# lrdboard_358v1.net
KiCad netlist of a schematic drawn in EAGLE
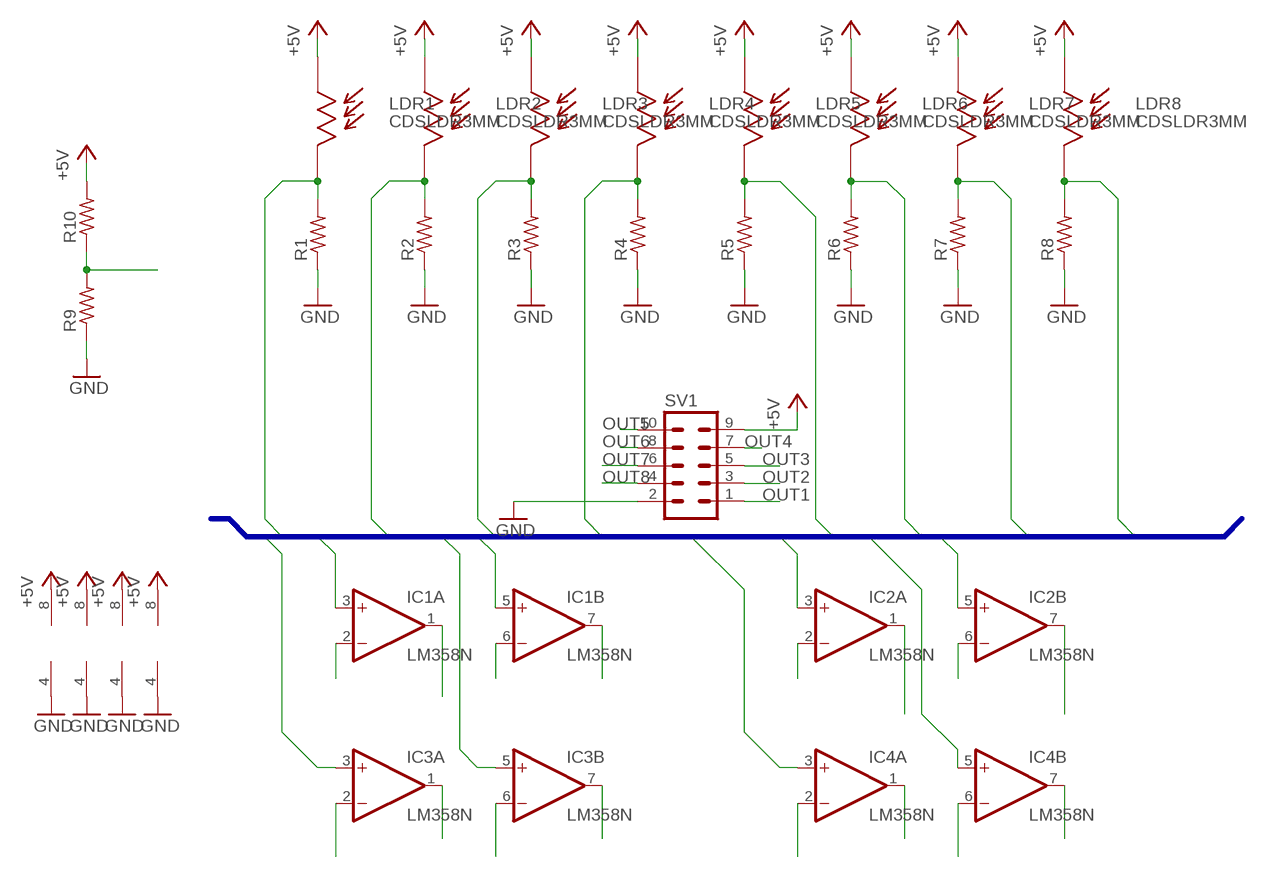
[diagram p0: schematic, sheet 1]

(export (version "E")
  (design (tool "Eeschema 10.0.6"))
  (components
    (comp (ref "IC1")
      (value "LM358N")
      (footprint "eagle-import:DIL08")
      (libsource (lib "eagle-import") (part "LM358N"))
    )
    (comp (ref "IC2")
      (value "LM358N")
      (footprint "eagle-import:DIL08")
      (libsource (lib "eagle-import") (part "LM358N"))
    )
    (comp (ref "IC3")
      (value "LM358N")
      (footprint "eagle-import:DIL08")
      (libsource (lib "eagle-import") (part "LM358N"))
    )
    (comp (ref "IC4")
      (value "LM358N")
      (footprint "eagle-import:DIL08")
      (libsource (lib "eagle-import") (part "LM358N"))
    )
    (comp (ref "LDR1")
      (value "CDSLDR3MM")
      (footprint "eagle-import:LDR3MM")
      (libsource (lib "eagle-import") (part "CDSLDR3MM"))
    )
    (comp (ref "LDR2")
      (value "CDSLDR3MM")
      (footprint "eagle-import:LDR3MM")
      (libsource (lib "eagle-import") (part "CDSLDR3MM"))
    )
    (comp (ref "LDR3")
      (value "CDSLDR3MM")
      (footprint "eagle-import:LDR3MM")
      (libsource (lib "eagle-import") (part "CDSLDR3MM"))
    )
    (comp (ref "LDR4")
      (value "CDSLDR3MM")
      (footprint "eagle-import:LDR3MM")
      (libsource (lib "eagle-import") (part "CDSLDR3MM"))
    )
    (comp (ref "LDR5")
      (value "CDSLDR3MM")
      (footprint "eagle-import:LDR3MM")
      (libsource (lib "eagle-import") (part "CDSLDR3MM"))
    )
    (comp (ref "LDR6")
      (value "CDSLDR3MM")
      (footprint "eagle-import:LDR3MM")
      (libsource (lib "eagle-import") (part "CDSLDR3MM"))
    )
    (comp (ref "LDR7")
      (value "CDSLDR3MM")
      (footprint "eagle-import:LDR3MM")
      (libsource (lib "eagle-import") (part "CDSLDR3MM"))
    )
    (comp (ref "LDR8")
      (value "CDSLDR3MM")
      (footprint "eagle-import:LDR3MM")
      (libsource (lib "eagle-import") (part "CDSLDR3MM"))
    )
    (comp (ref "R1")
      (value "RESISTOR0207/10")
      (footprint "eagle-import:0207_10")
      (libsource (lib "eagle-import") (part "RESISTOR0207/10"))
    )
    (comp (ref "R2")
      (value "RESISTOR0207/10")
      (footprint "eagle-import:0207_10")
      (libsource (lib "eagle-import") (part "RESISTOR0207/10"))
    )
    (comp (ref "R3")
      (value "RESISTOR0207/10")
      (footprint "eagle-import:0207_10")
      (libsource (lib "eagle-import") (part "RESISTOR0207/10"))
    )
    (comp (ref "R4")
      (value "RESISTOR0207/10")
      (footprint "eagle-import:0207_10")
      (libsource (lib "eagle-import") (part "RESISTOR0207/10"))
    )
    (comp (ref "R5")
      (value "RESISTOR0207/10")
      (footprint "eagle-import:0207_10")
      (libsource (lib "eagle-import") (part "RESISTOR0207/10"))
    )
    (comp (ref "R6")
      (value "RESISTOR0207/10")
      (footprint "eagle-import:0207_10")
      (libsource (lib "eagle-import") (part "RESISTOR0207/10"))
    )
    (comp (ref "R7")
      (value "RESISTOR0207/10")
      (footprint "eagle-import:0207_10")
      (libsource (lib "eagle-import") (part "RESISTOR0207/10"))
    )
    (comp (ref "R8")
      (value "RESISTOR0207/10")
      (footprint "eagle-import:0207_10")
      (libsource (lib "eagle-import") (part "RESISTOR0207/10"))
    )
    (comp (ref "R9")
      (value "RESISTOR0207/10")
      (footprint "eagle-import:0207_10")
      (libsource (lib "eagle-import") (part "RESISTOR0207/10"))
    )
    (comp (ref "R10")
      (value "RESISTOR0207/10")
      (footprint "eagle-import:0207_10")
      (libsource (lib "eagle-import") (part "RESISTOR0207/10"))
    )
    (comp (ref "SV1")
      (value "MA05-2")
      (footprint "eagle-import:MA05-2")
      (libsource (lib "eagle-import") (part "MA05-2"))
    )
  )
  (nets
    (net (code "1") (name "+5V") (class "Default")
      (node (ref "IC1") (pin "8") (pinfunction "V+_8") (pintype "power_in"))
      (node (ref "IC2") (pin "8") (pinfunction "V+_8") (pintype "power_in"))
      (node (ref "IC3") (pin "8") (pinfunction "V+_8") (pintype "power_in"))
      (node (ref "IC4") (pin "8") (pinfunction "V+_8") (pintype "power_in"))
      (node (ref "LDR1") (pin "P$1") (pinfunction "P$1_P$1") (pintype "bidirectional"))
      (node (ref "LDR2") (pin "P$1") (pinfunction "P$1_P$1") (pintype "bidirectional"))
      (node (ref "LDR3") (pin "P$1") (pinfunction "P$1_P$1") (pintype "bidirectional"))
      (node (ref "LDR4") (pin "P$1") (pinfunction "P$1_P$1") (pintype "bidirectional"))
      (node (ref "LDR5") (pin "P$1") (pinfunction "P$1_P$1") (pintype "bidirectional"))
      (node (ref "LDR6") (pin "P$1") (pinfunction "P$1_P$1") (pintype "bidirectional"))
      (node (ref "LDR7") (pin "P$1") (pinfunction "P$1_P$1") (pintype "bidirectional"))
      (node (ref "LDR8") (pin "P$1") (pinfunction "P$1_P$1") (pintype "bidirectional"))
      (node (ref "R10") (pin "2") (pinfunction "2_2") (pintype "passive"))
      (node (ref "SV1") (pin "9") (pinfunction "9_9") (pintype "passive"))
    )
    (net (code "2") (name "/1") (class "Default")
      (node (ref "IC1") (pin "3") (pinfunction "+IN_3") (pintype "input"))
      (node (ref "LDR1") (pin "P$2") (pinfunction "P$2_P$2") (pintype "bidirectional"))
      (node (ref "R1") (pin "2") (pinfunction "2_2") (pintype "passive"))
    )
    (net (code "3") (name "/2") (class "Default")
      (node (ref "IC1") (pin "5") (pinfunction "+IN_5") (pintype "input"))
      (node (ref "LDR2") (pin "P$2") (pinfunction "P$2_P$2") (pintype "bidirectional"))
      (node (ref "R2") (pin "2") (pinfunction "2_2") (pintype "passive"))
    )
    (net (code "4") (name "/3") (class "Default")
      (node (ref "IC2") (pin "3") (pinfunction "+IN_3") (pintype "input"))
      (node (ref "LDR3") (pin "P$2") (pinfunction "P$2_P$2") (pintype "bidirectional"))
      (node (ref "R3") (pin "2") (pinfunction "2_2") (pintype "passive"))
    )
    (net (code "5") (name "/4") (class "Default")
      (node (ref "IC2") (pin "5") (pinfunction "+IN_5") (pintype "input"))
      (node (ref "LDR4") (pin "P$2") (pinfunction "P$2_P$2") (pintype "bidirectional"))
      (node (ref "R4") (pin "2") (pinfunction "2_2") (pintype "passive"))
    )
    (net (code "6") (name "/5") (class "Default")
      (node (ref "IC3") (pin "3") (pinfunction "+IN_3") (pintype "input"))
      (node (ref "LDR5") (pin "P$2") (pinfunction "P$2_P$2") (pintype "bidirectional"))
      (node (ref "R5") (pin "2") (pinfunction "2_2") (pintype "passive"))
    )
    (net (code "7") (name "/6") (class "Default")
      (node (ref "IC3") (pin "5") (pinfunction "+IN_5") (pintype "input"))
      (node (ref "LDR6") (pin "P$2") (pinfunction "P$2_P$2") (pintype "bidirectional"))
      (node (ref "R6") (pin "2") (pinfunction "2_2") (pintype "passive"))
    )
    (net (code "8") (name "/7") (class "Default")
      (node (ref "IC4") (pin "3") (pinfunction "+IN_3") (pintype "input"))
      (node (ref "LDR7") (pin "P$2") (pinfunction "P$2_P$2") (pintype "bidirectional"))
      (node (ref "R7") (pin "2") (pinfunction "2_2") (pintype "passive"))
    )
    (net (code "9") (name "/8") (class "Default")
      (node (ref "IC4") (pin "5") (pinfunction "+IN_5") (pintype "input"))
      (node (ref "LDR8") (pin "P$2") (pinfunction "P$2_P$2") (pintype "bidirectional"))
      (node (ref "R8") (pin "2") (pinfunction "2_2") (pintype "passive"))
    )
    (net (code "10") (name "/MID") (class "Default")
      (node (ref "IC1") (pin "2") (pinfunction "-IN_2") (pintype "input"))
      (node (ref "IC1") (pin "6") (pinfunction "-IN_6") (pintype "input"))
      (node (ref "IC2") (pin "2") (pinfunction "-IN_2") (pintype "input"))
      (node (ref "IC2") (pin "6") (pinfunction "-IN_6") (pintype "input"))
      (node (ref "IC3") (pin "2") (pinfunction "-IN_2") (pintype "input"))
      (node (ref "IC3") (pin "6") (pinfunction "-IN_6") (pintype "input"))
      (node (ref "IC4") (pin "2") (pinfunction "-IN_2") (pintype "input"))
      (node (ref "IC4") (pin "6") (pinfunction "-IN_6") (pintype "input"))
      (node (ref "R10") (pin "1") (pinfunction "1_1") (pintype "passive"))
      (node (ref "R9") (pin "2") (pinfunction "2_2") (pintype "passive"))
    )
    (net (code "11") (name "/OUT1") (class "Default")
      (node (ref "IC1") (pin "1") (pinfunction "OUT_1") (pintype "output"))
      (node (ref "SV1") (pin "1") (pinfunction "1_1") (pintype "passive"))
    )
    (net (code "12") (name "/OUT2") (class "Default")
      (node (ref "IC1") (pin "7") (pinfunction "OUT_7") (pintype "output"))
      (node (ref "SV1") (pin "3") (pinfunction "3_3") (pintype "passive"))
    )
    (net (code "13") (name "/OUT3") (class "Default")
      (node (ref "IC2") (pin "1") (pinfunction "OUT_1") (pintype "output"))
      (node (ref "SV1") (pin "5") (pinfunction "5_5") (pintype "passive"))
    )
    (net (code "14") (name "/OUT4") (class "Default")
      (node (ref "IC2") (pin "7") (pinfunction "OUT_7") (pintype "output"))
      (node (ref "SV1") (pin "7") (pinfunction "7_7") (pintype "passive"))
    )
    (net (code "15") (name "/OUT5") (class "Default")
      (node (ref "IC3") (pin "1") (pinfunction "OUT_1") (pintype "output"))
      (node (ref "SV1") (pin "10") (pinfunction "10_10") (pintype "passive"))
    )
    (net (code "16") (name "/OUT6") (class "Default")
      (node (ref "IC3") (pin "7") (pinfunction "OUT_7") (pintype "output"))
      (node (ref "SV1") (pin "8") (pinfunction "8_8") (pintype "passive"))
    )
    (net (code "17") (name "/OUT7") (class "Default")
      (node (ref "IC4") (pin "1") (pinfunction "OUT_1") (pintype "output"))
      (node (ref "SV1") (pin "6") (pinfunction "6_6") (pintype "passive"))
    )
    (net (code "18") (name "/OUT8") (class "Default")
      (node (ref "IC4") (pin "7") (pinfunction "OUT_7") (pintype "output"))
      (node (ref "SV1") (pin "4") (pinfunction "4_4") (pintype "passive"))
    )
    (net (code "19") (name "GND") (class "Default")
      (node (ref "IC1") (pin "4") (pinfunction "V-_4") (pintype "power_in"))
      (node (ref "IC2") (pin "4") (pinfunction "V-_4") (pintype "power_in"))
      (node (ref "IC3") (pin "4") (pinfunction "V-_4") (pintype "power_in"))
      (node (ref "IC4") (pin "4") (pinfunction "V-_4") (pintype "power_in"))
      (node (ref "R1") (pin "1") (pinfunction "1_1") (pintype "passive"))
      (node (ref "R2") (pin "1") (pinfunction "1_1") (pintype "passive"))
      (node (ref "R3") (pin "1") (pinfunction "1_1") (pintype "passive"))
      (node (ref "R4") (pin "1") (pinfunction "1_1") (pintype "passive"))
      (node (ref "R5") (pin "1") (pinfunction "1_1") (pintype "passive"))
      (node (ref "R6") (pin "1") (pinfunction "1_1") (pintype "passive"))
      (node (ref "R7") (pin "1") (pinfunction "1_1") (pintype "passive"))
      (node (ref "R8") (pin "1") (pinfunction "1_1") (pintype "passive"))
      (node (ref "R9") (pin "1") (pinfunction "1_1") (pintype "passive"))
      (node (ref "SV1") (pin "2") (pinfunction "2_2") (pintype "passive"))
    )
  )
)
